# PALM.net
KiCad netlist of a schematic drawn in EAGLE
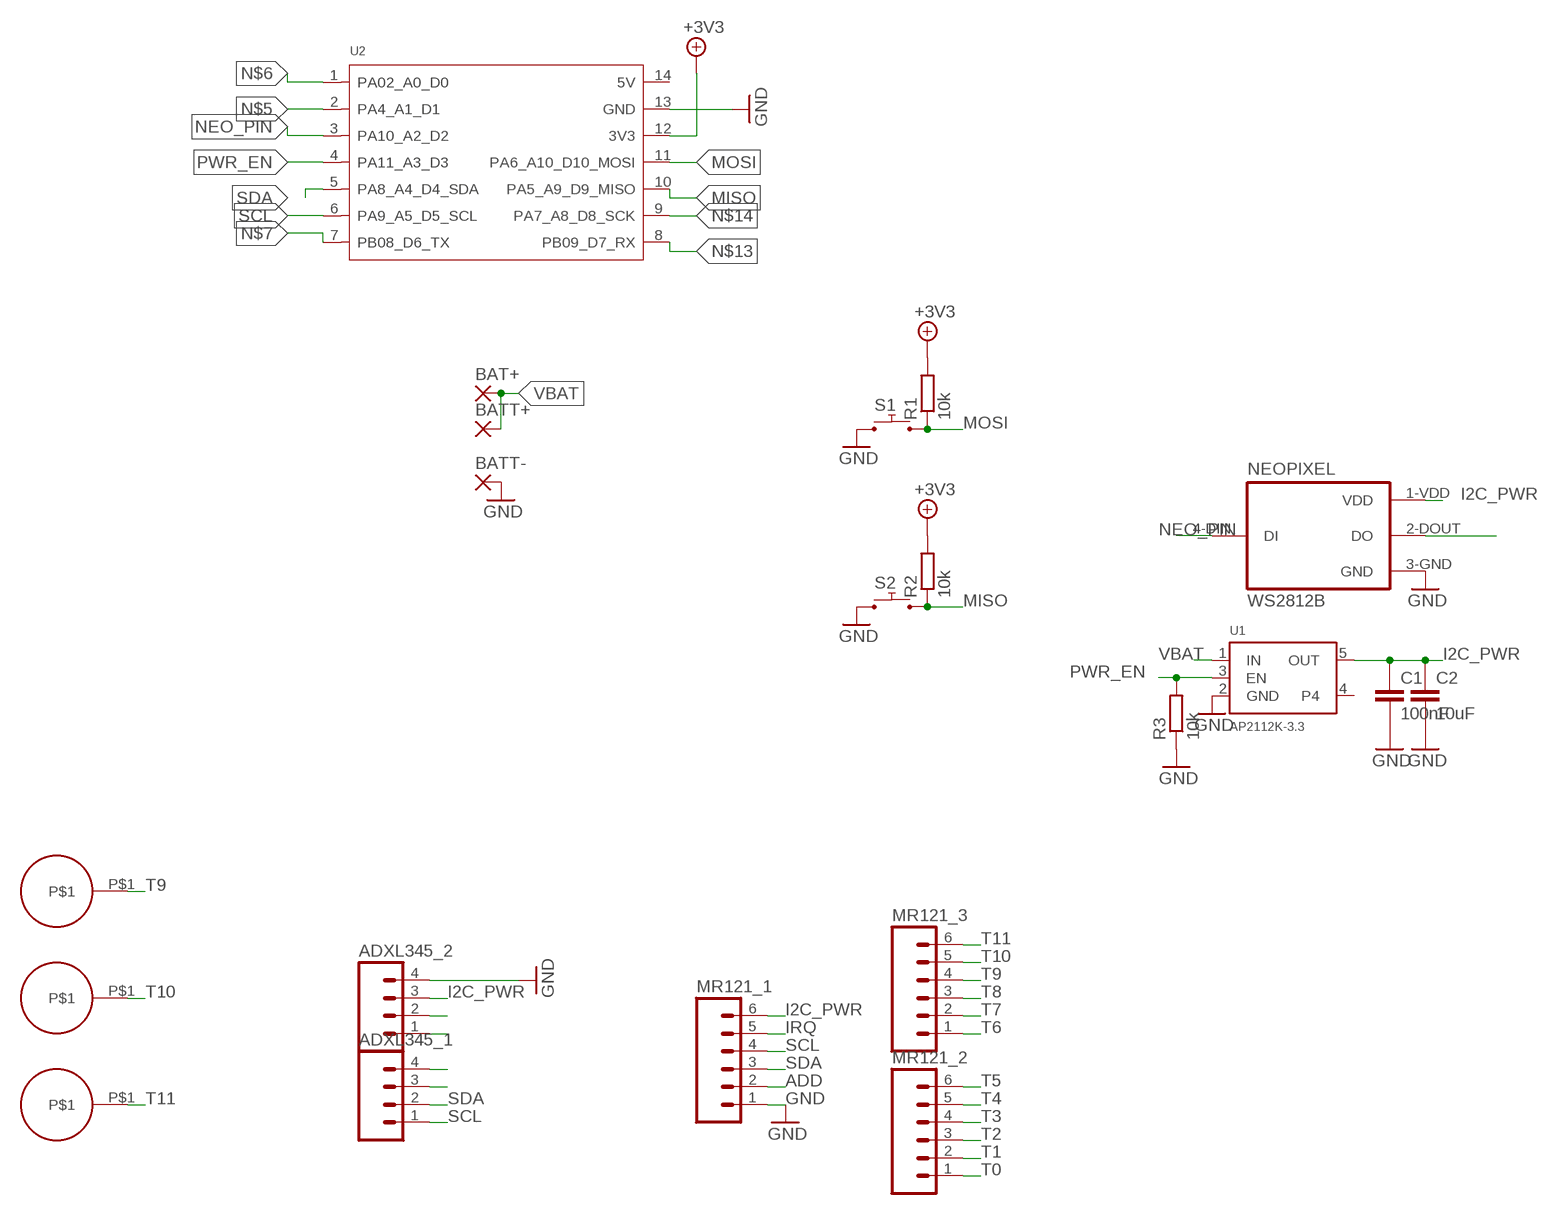
[diagram p0: schematic, sheet 1]

(export (version "E")
  (design (tool "Eeschema 10.0.6"))
  (components
    (comp (ref "ADXL345_1")
      (value "M04SMD_STRAIGHT_COMBO")
      (footprint "eagle-import:1X04_SMD_STRAIGHT_COMBO")
      (libsource (lib "eagle-import") (part "M04SMD_STRAIGHT_COMBO"))
    )
    (comp (ref "ADXL345_2")
      (value "M04SMD_STRAIGHT_COMBO")
      (footprint "eagle-import:1X04_SMD_STRAIGHT_COMBO")
      (libsource (lib "eagle-import") (part "M04SMD_STRAIGHT_COMBO"))
    )
    (comp (ref "BAT+")
      (value "SMD2")
      (footprint "eagle-import:SMD1,27-2,54")
      (libsource (lib "eagle-import") (part "SMD2"))
    )
    (comp (ref "BATT+")
      (value "SMD2")
      (footprint "eagle-import:SMD1,27-2,54")
      (libsource (lib "eagle-import") (part "SMD2"))
    )
    (comp (ref "BATT-")
      (value "SMD2")
      (footprint "eagle-import:SMD1,27-2,54")
      (libsource (lib "eagle-import") (part "SMD2"))
    )
    (comp (ref "C1")
      (value "100nF")
      (footprint "eagle-import:CAPACITOR0805")
      (libsource (lib "eagle-import") (part "CAPACITOR0805"))
    )
    (comp (ref "C2")
      (value "10uF")
      (footprint "eagle-import:CAPACITOR0805")
      (libsource (lib "eagle-import") (part "CAPACITOR0805"))
    )
    (comp (ref "H2")
      (value "FEROS_HEATHOLE")
      (footprint "eagle-import:FEROS_HEATHOLE3.2")
      (libsource (lib "eagle-import") (part "FEROS_HEATHOLE"))
    )
    (comp (ref "H3")
      (value "FEROS_HEATHOLE")
      (footprint "eagle-import:FEROS_HEATHOLE3.2")
      (libsource (lib "eagle-import") (part "FEROS_HEATHOLE"))
    )
    (comp (ref "H4")
      (value "FEROS_HEATHOLE")
      (footprint "eagle-import:FEROS_HEATHOLE3.2")
      (libsource (lib "eagle-import") (part "FEROS_HEATHOLE"))
    )
    (comp (ref "MR121_1")
      (value "M06SMD-STRAIGHT-COMBO")
      (footprint "eagle-import:1X06_SMD_STRAIGHT_COMBO")
      (libsource (lib "eagle-import") (part "M06SMD-STRAIGHT-COMBO"))
    )
    (comp (ref "MR121_2")
      (value "M06SMD-STRAIGHT-COMBO")
      (footprint "eagle-import:1X06_SMD_STRAIGHT_COMBO")
      (libsource (lib "eagle-import") (part "M06SMD-STRAIGHT-COMBO"))
    )
    (comp (ref "MR121_3")
      (value "M06SMD-STRAIGHT-COMBO")
      (footprint "eagle-import:1X06_SMD_STRAIGHT_COMBO")
      (libsource (lib "eagle-import") (part "M06SMD-STRAIGHT-COMBO"))
    )
    (comp (ref "NEOPIXEL")
      (value "WS2812B")
      (footprint "eagle-import:WS2812B")
      (libsource (lib "eagle-import") (part "WS2812B"))
    )
    (comp (ref "R1")
      (value "10k")
      (footprint "eagle-import:0805")
      (libsource (lib "eagle-import") (part "RESISTOR0805"))
    )
    (comp (ref "R2")
      (value "10k")
      (footprint "eagle-import:0805")
      (libsource (lib "eagle-import") (part "RESISTOR0805"))
    )
    (comp (ref "R3")
      (value "10k")
      (footprint "eagle-import:0805")
      (libsource (lib "eagle-import") (part "RESISTOR0805"))
    )
    (comp (ref "S1")
      (value "PUSH_MOMENTARY_THT_6X6MM")
      (footprint "eagle-import:TACTILE-PTH")
      (libsource (lib "eagle-import") (part "PUSH_MOMENTARY_THT_6X6MM"))
    )
    (comp (ref "S2")
      (value "PUSH_MOMENTARY_THT_6X6MM")
      (footprint "eagle-import:TACTILE-PTH")
      (libsource (lib "eagle-import") (part "PUSH_MOMENTARY_THT_6X6MM"))
    )
    (comp (ref "U1")
      (value "AP2112K-3.3")
      (footprint "eagle-import:MICROBUILDER_SOT23-5")
      (libsource (lib "eagle-import") (part "MICROBUILDER_VREG_SOT23-5"))
    )
    (comp (ref "U2")
      (value "MOUDLE-SEEEDUINO-XIAO-ESP32S3-SMD")
      (footprint "eagle-import:MOUDLE14P-SMD-2.54-21X17.8MM")
      (libsource (lib "eagle-import") (part "MOUDLE-SEEEDUINO-XIAO-ESP32S3-SMD"))
    )
  )
  (nets
    (net (code "1") (name "+3V3") (class "Default")
      (node (ref "R1") (pin "2") (pinfunction "2_2") (pintype "passive"))
      (node (ref "R2") (pin "2") (pinfunction "2_2") (pintype "passive"))
      (node (ref "U2") (pin "12") (pinfunction "3V3_12") (pintype "bidirectional"))
    )
    (net (code "2") (name "/ADD") (class "Default")
      (node (ref "MR121_1") (pin "2") (pinfunction "2_2") (pintype "passive"))
    )
    (net (code "3") (name "/I2C_PWR") (class "Default")
      (node (ref "ADXL345_2") (pin "3") (pinfunction "3_3") (pintype "passive"))
      (node (ref "C1") (pin "1") (pinfunction "1_1") (pintype "passive"))
      (node (ref "C2") (pin "1") (pinfunction "1_1") (pintype "passive"))
      (node (ref "MR121_1") (pin "6") (pinfunction "6_6") (pintype "passive"))
      (node (ref "NEOPIXEL") (pin "1-VDD") (pinfunction "VDD_1-VDD") (pintype "power_in"))
      (node (ref "U1") (pin "5") (pinfunction "OUT_5") (pintype "power_in"))
    )
    (net (code "4") (name "/IRQ") (class "Default")
      (node (ref "MR121_1") (pin "5") (pinfunction "5_5") (pintype "passive"))
    )
    (net (code "5") (name "/T0") (class "Default")
      (node (ref "MR121_2") (pin "1") (pinfunction "1_1") (pintype "passive"))
    )
    (net (code "6") (name "/T1") (class "Default")
      (node (ref "MR121_2") (pin "2") (pinfunction "2_2") (pintype "passive"))
    )
    (net (code "7") (name "/T2") (class "Default")
      (node (ref "MR121_2") (pin "3") (pinfunction "3_3") (pintype "passive"))
    )
    (net (code "8") (name "/T3") (class "Default")
      (node (ref "MR121_2") (pin "4") (pinfunction "4_4") (pintype "passive"))
    )
    (net (code "9") (name "/T4") (class "Default")
      (node (ref "MR121_2") (pin "5") (pinfunction "5_5") (pintype "passive"))
    )
    (net (code "10") (name "/T5") (class "Default")
      (node (ref "MR121_2") (pin "6") (pinfunction "6_6") (pintype "passive"))
    )
    (net (code "11") (name "/T6") (class "Default")
      (node (ref "MR121_3") (pin "1") (pinfunction "1_1") (pintype "passive"))
    )
    (net (code "12") (name "/T7") (class "Default")
      (node (ref "MR121_3") (pin "2") (pinfunction "2_2") (pintype "passive"))
    )
    (net (code "13") (name "/T8") (class "Default")
      (node (ref "MR121_3") (pin "3") (pinfunction "3_3") (pintype "passive"))
    )
    (net (code "14") (name "/T9") (class "Default")
      (node (ref "H4") (pin "P$1") (pinfunction "P$1_P$1") (pintype "bidirectional"))
      (node (ref "MR121_3") (pin "4") (pinfunction "4_4") (pintype "passive"))
    )
    (net (code "15") (name "/T10") (class "Default")
      (node (ref "H3") (pin "P$1") (pinfunction "P$1_P$1") (pintype "bidirectional"))
      (node (ref "MR121_3") (pin "5") (pinfunction "5_5") (pintype "passive"))
    )
    (net (code "16") (name "/T11") (class "Default")
      (node (ref "H2") (pin "P$1") (pinfunction "P$1_P$1") (pintype "bidirectional"))
      (node (ref "MR121_3") (pin "6") (pinfunction "6_6") (pintype "passive"))
    )
    (net (code "17") (name "GND") (class "Default")
      (node (ref "ADXL345_2") (pin "4") (pinfunction "4_4") (pintype "passive"))
      (node (ref "BATT-") (pin "1") (pinfunction "P_1") (pintype "passive"))
      (node (ref "C1") (pin "2") (pinfunction "2_2") (pintype "passive"))
      (node (ref "C2") (pin "2") (pinfunction "2_2") (pintype "passive"))
      (node (ref "MR121_1") (pin "1") (pinfunction "1_1") (pintype "passive"))
      (node (ref "NEOPIXEL") (pin "3-GND") (pinfunction "GND_3-GND") (pintype "power_in"))
      (node (ref "R3") (pin "1") (pinfunction "1_1") (pintype "passive"))
      (node (ref "S1") (pin "1") (pinfunction "1_1") (pintype "passive"))
      (node (ref "S1") (pin "2") (pinfunction "1_2") (pintype "passive"))
      (node (ref "S2") (pin "1") (pinfunction "1_1") (pintype "passive"))
      (node (ref "S2") (pin "2") (pinfunction "1_2") (pintype "passive"))
      (node (ref "U1") (pin "2") (pinfunction "GND_2") (pintype "power_in"))
      (node (ref "U2") (pin "13") (pinfunction "GND_13") (pintype "bidirectional"))
    )
    (net (code "18") (name "MISO") (class "Default")
      (node (ref "R2") (pin "1") (pinfunction "1_1") (pintype "passive"))
      (node (ref "S2") (pin "3") (pinfunction "2_3") (pintype "passive"))
      (node (ref "S2") (pin "4") (pinfunction "2_4") (pintype "passive"))
      (node (ref "U2") (pin "10") (pinfunction "PA5_A9_D9_MISO_10") (pintype "bidirectional"))
    )
    (net (code "19") (name "MOSI") (class "Default")
      (node (ref "R1") (pin "1") (pinfunction "1_1") (pintype "passive"))
      (node (ref "S1") (pin "3") (pinfunction "2_3") (pintype "passive"))
      (node (ref "S1") (pin "4") (pinfunction "2_4") (pintype "passive"))
      (node (ref "U2") (pin "11") (pinfunction "PA6_A10_D10_MOSI_11") (pintype "bidirectional"))
    )
    (net (code "20") (name "N$5") (class "Default")
      (node (ref "U2") (pin "2") (pinfunction "PA4_A1_D1_2") (pintype "bidirectional"))
    )
    (net (code "21") (name "N$6") (class "Default")
      (node (ref "U2") (pin "1") (pinfunction "PA02_A0_D0_1") (pintype "bidirectional"))
    )
    (net (code "22") (name "N$7") (class "Default")
      (node (ref "U2") (pin "7") (pinfunction "PB08_D6_TX_7") (pintype "bidirectional"))
    )
    (net (code "23") (name "N$13") (class "Default")
      (node (ref "U2") (pin "8") (pinfunction "PB09_D7_RX_8") (pintype "bidirectional"))
    )
    (net (code "24") (name "N$14") (class "Default")
      (node (ref "U2") (pin "9") (pinfunction "PA7_A8_D8_SCK_9") (pintype "bidirectional"))
    )
    (net (code "25") (name "NEO_PIN") (class "Default")
      (node (ref "NEOPIXEL") (pin "4-DIN") (pinfunction "DI_4-DIN") (pintype "input"))
      (node (ref "U2") (pin "3") (pinfunction "PA10_A2_D2_3") (pintype "bidirectional"))
    )
    (net (code "26") (name "PWR_EN") (class "Default")
      (node (ref "R3") (pin "2") (pinfunction "2_2") (pintype "passive"))
      (node (ref "U1") (pin "3") (pinfunction "EN_3") (pintype "input"))
      (node (ref "U2") (pin "4") (pinfunction "PA11_A3_D3_4") (pintype "bidirectional"))
    )
    (net (code "27") (name "SCL") (class "Default")
      (node (ref "ADXL345_1") (pin "1") (pinfunction "1_1") (pintype "passive"))
      (node (ref "MR121_1") (pin "4") (pinfunction "4_4") (pintype "passive"))
      (node (ref "U2") (pin "6") (pinfunction "PA9_A5_D5_SCL_6") (pintype "bidirectional"))
    )
    (net (code "28") (name "SDA") (class "Default")
      (node (ref "ADXL345_1") (pin "2") (pinfunction "2_2") (pintype "passive"))
      (node (ref "MR121_1") (pin "3") (pinfunction "3_3") (pintype "passive"))
      (node (ref "U2") (pin "5") (pinfunction "PA8_A4_D4_SDA_5") (pintype "bidirectional"))
    )
    (net (code "29") (name "VBAT") (class "Default")
      (node (ref "BAT+") (pin "1") (pinfunction "P_1") (pintype "passive"))
      (node (ref "BATT+") (pin "1") (pinfunction "P_1") (pintype "passive"))
      (node (ref "U1") (pin "1") (pinfunction "IN_1") (pintype "power_in"))
    )
    (net (code "30") (name "unconnected-(ADXL345_1-Pad3)") (class "Default")
      (node (ref "ADXL345_1") (pin "3") (pinfunction "3_3") (pintype "passive"))
    )
    (net (code "31") (name "unconnected-(ADXL345_1-Pad4)") (class "Default")
      (node (ref "ADXL345_1") (pin "4") (pinfunction "4_4") (pintype "passive"))
    )
    (net (code "32") (name "unconnected-(ADXL345_2-Pad1)") (class "Default")
      (node (ref "ADXL345_2") (pin "1") (pinfunction "1_1") (pintype "passive"))
    )
    (net (code "33") (name "unconnected-(ADXL345_2-Pad2)") (class "Default")
      (node (ref "ADXL345_2") (pin "2") (pinfunction "2_2") (pintype "passive"))
    )
    (net (code "34") (name "unconnected-(NEOPIXEL-DO-Pad2-DOUT)") (class "Default")
      (node (ref "NEOPIXEL") (pin "2-DOUT") (pinfunction "DO_2-DOUT") (pintype "output"))
    )
    (net (code "35") (name "unconnected-(U1-P4-Pad4)") (class "Default")
      (node (ref "U1") (pin "4") (pinfunction "P4_4") (pintype "bidirectional"))
    )
    (net (code "36") (name "unconnected-(U2-5V-Pad14)") (class "Default")
      (node (ref "U2") (pin "14") (pinfunction "5V_14") (pintype "bidirectional"))
    )
  )
)
